# STM32Fx.net
KiCad netlist of a schematic drawn in Altium Designer
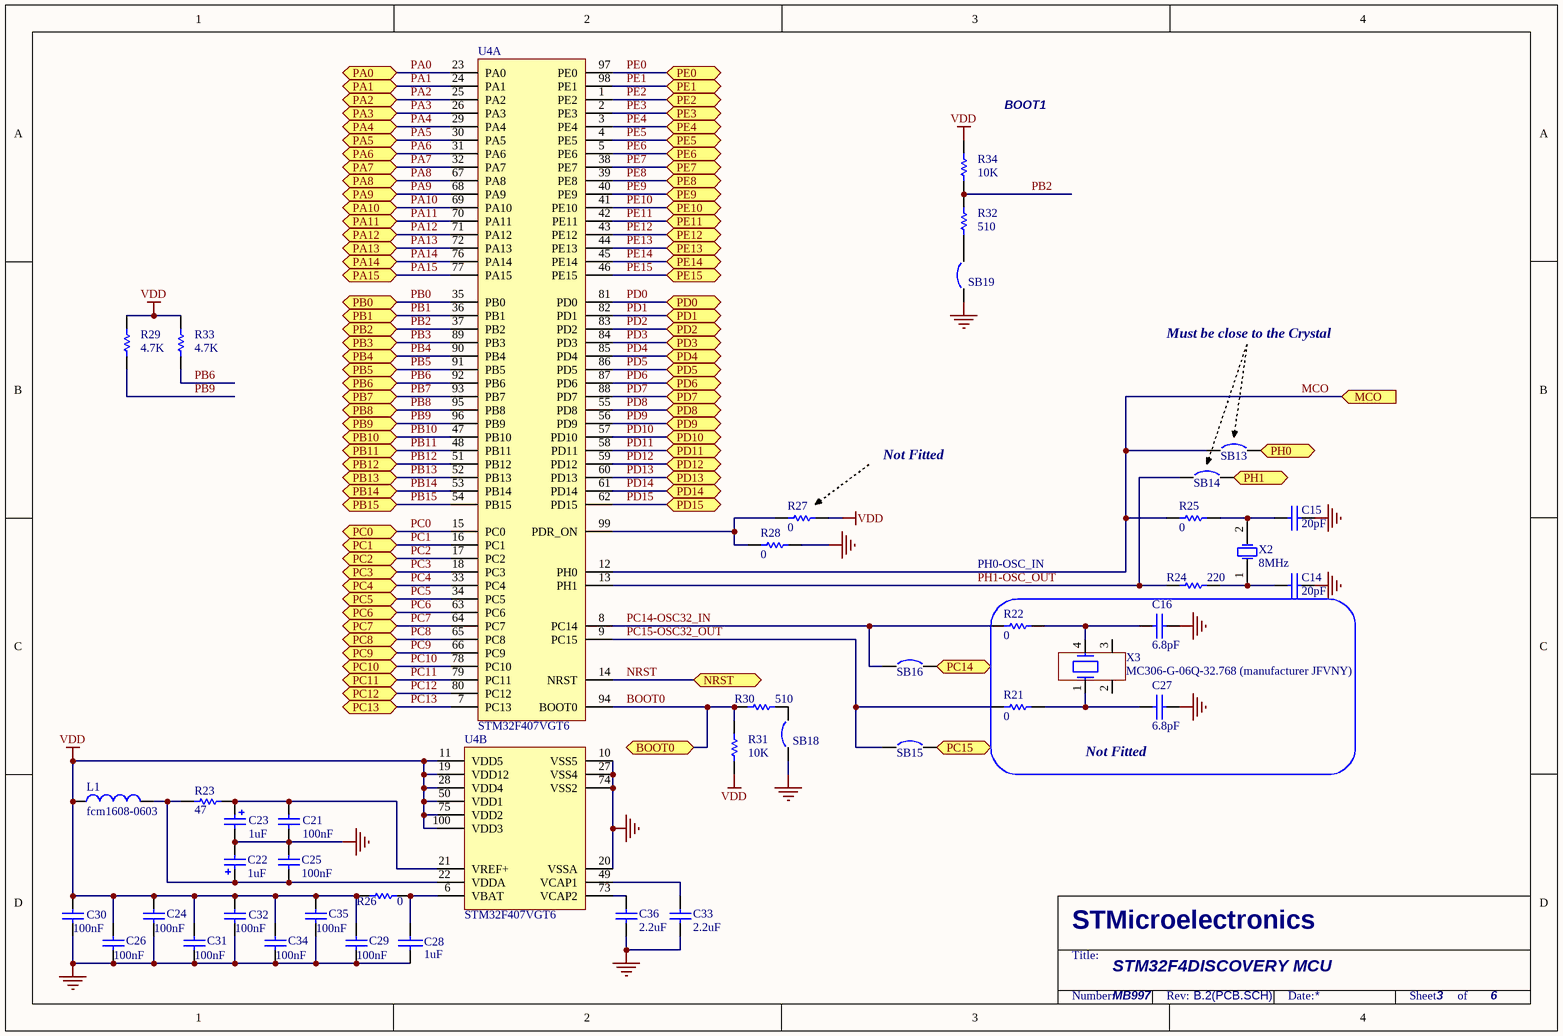
[diagram p0: STM32Fx.SchDoc]

(export (version "E")
  (design (tool "Eeschema 10.0.6"))
  (components
    (comp (ref "C14")
      (value "20pF")
      (footprint "0603C")
      (description "Capacitor")
      (libsource (lib "*") (part "CAP"))
    )
    (comp (ref "C15")
      (value "20pF")
      (footprint "0603C")
      (description "Capacitor")
      (libsource (lib "*") (part "CAP"))
    )
    (comp (ref "C16")
      (value "6.8pF")
      (footprint "0603C")
      (description "Capacitor")
      (libsource (lib "") (part "CAP_1"))
    )
    (comp (ref "C21")
      (value "100nF")
      (footprint "0603C")
      (description "Capacitor")
      (fields (field (name "PUBLISHER") "Altium Limited"))
      (libsource (lib "MB915_1") (part "Cap"))
    )
    (comp (ref "C22")
      (value "1uF")
      (footprint "CASE-AA")
      (description "Polarized Capacitor (Radial)")
      (fields (field (name "PUBLISHER") "Altium Limited"))
      (libsource (lib "Miscellaneous Devices") (part "Cap Pol1"))
    )
    (comp (ref "C23")
      (value "1uF")
      (footprint "CASE-AA")
      (description "Polarized Capacitor (Radial)")
      (fields (field (name "PUBLISHER") "Altium Limited"))
      (libsource (lib "Miscellaneous Devices") (part "Cap Pol1"))
    )
    (comp (ref "C24")
      (value "100nF")
      (footprint "0603C")
      (description "Capacitor")
      (fields (field (name "PUBLISHER") "Altium Limited"))
      (libsource (lib "MB915_1") (part "Cap"))
    )
    (comp (ref "C25")
      (value "100nF")
      (footprint "0603C")
      (description "Capacitor")
      (fields (field (name "PUBLISHER") "Altium Limited"))
      (libsource (lib "MB915_1") (part "Cap"))
    )
    (comp (ref "C26")
      (value "100nF")
      (footprint "0603C")
      (description "Capacitor")
      (fields (field (name "PUBLISHER") "Altium Limited"))
      (libsource (lib "MB915_1") (part "Cap"))
    )
    (comp (ref "C27")
      (value "6.8pF")
      (footprint "0603C")
      (description "Capacitor")
      (libsource (lib "") (part "CAP_1"))
    )
    (comp (ref "C28")
      (value "1uF")
      (footprint "0603C")
      (description "Capacitor")
      (libsource (lib "*") (part "CAP"))
    )
    (comp (ref "C29")
      (value "100nF")
      (footprint "0603C")
      (description "Capacitor")
      (fields (field (name "PUBLISHER") "Altium Limited"))
      (libsource (lib "MB915_1") (part "Cap"))
    )
    (comp (ref "C30")
      (value "100nF")
      (footprint "0603C")
      (description "Capacitor")
      (fields (field (name "PUBLISHER") "Altium Limited"))
      (libsource (lib "MB915_1") (part "Cap"))
    )
    (comp (ref "C31")
      (value "100nF")
      (footprint "0603C")
      (description "Capacitor")
      (fields (field (name "PUBLISHER") "Altium Limited"))
      (libsource (lib "MB915_1") (part "Cap"))
    )
    (comp (ref "C32")
      (value "100nF")
      (footprint "0603C")
      (description "Capacitor")
      (fields (field (name "PUBLISHER") "Altium Limited"))
      (libsource (lib "MB915_1") (part "Cap"))
    )
    (comp (ref "C33")
      (value "2.2uF")
      (footprint "CASE-A")
      (description "Low ESR Ceramic Capacitor (X7R)")
      (fields (field (name "PUBLISHER") "Altium Limited"))
      (libsource (lib "MB997") (part "Cap Low ESR"))
    )
    (comp (ref "C34")
      (value "100nF")
      (footprint "0603C")
      (description "Capacitor")
      (fields (field (name "PUBLISHER") "Altium Limited"))
      (libsource (lib "MB915_1") (part "Cap"))
    )
    (comp (ref "C35")
      (value "100nF")
      (footprint "0603C")
      (description "Capacitor")
      (fields (field (name "PUBLISHER") "Altium Limited"))
      (libsource (lib "MB915_1") (part "Cap"))
    )
    (comp (ref "C36")
      (value "2.2uF")
      (footprint "CASE-A")
      (description "Low ESR Ceramic Capacitor (X7R)")
      (fields (field (name "PUBLISHER") "Altium Limited"))
      (libsource (lib "MB997") (part "Cap Low ESR"))
    )
    (comp (ref "L1")
      (value "fcm1608-0603")
      (footprint "0603L")
      (description "Inductor")
      (fields (field (name "PUBLISHER") "Altium Limited"))
      (libsource (lib "Miscellaneous Devices") (part "Inductor"))
    )
    (comp (ref "R21")
      (value "0")
      (footprint "0603R")
      (description "Resistor")
      (fields (field (name "PUBLISHER") "Altium Limited"))
      (libsource (lib "Miscellaneous Devices") (part "Res1"))
    )
    (comp (ref "R22")
      (value "0")
      (footprint "0603R")
      (description "Resistor")
      (fields (field (name "PUBLISHER") "Altium Limited"))
      (libsource (lib "Miscellaneous Devices") (part "Res1"))
    )
    (comp (ref "R23")
      (value "47")
      (footprint "0603R")
      (description "Resistor")
      (fields (field (name "PUBLISHER") "Altium Limited"))
      (libsource (lib "Miscellaneous Devices") (part "Res1"))
    )
    (comp (ref "R24")
      (value "220")
      (footprint "0603R")
      (description "Resistor")
      (fields (field (name "PUBLISHER") "Altium Limited"))
      (libsource (lib "Miscellaneous Devices") (part "Res1"))
    )
    (comp (ref "R25")
      (value "0")
      (footprint "0603R")
      (description "Resistor")
      (fields (field (name "PUBLISHER") "Altium Limited"))
      (libsource (lib "Miscellaneous Devices") (part "Res1"))
    )
    (comp (ref "R26")
      (value "0")
      (footprint "0603R")
      (description "Resistor")
      (fields (field (name "PUBLISHER") "Altium Limited"))
      (libsource (lib "Miscellaneous Devices") (part "res1"))
    )
    (comp (ref "R27")
      (value "0")
      (footprint "0603R")
      (description "Resistor")
      (fields (field (name "PUBLISHER") "Altium Limited"))
      (libsource (lib "Miscellaneous Devices") (part "Res1"))
    )
    (comp (ref "R28")
      (value "0")
      (footprint "0603R")
      (description "Resistor")
      (fields (field (name "PUBLISHER") "Altium Limited"))
      (libsource (lib "Miscellaneous Devices") (part "Res1"))
    )
    (comp (ref "R29")
      (value "4.7K")
      (footprint "0402R")
      (description "Resistor")
      (fields (field (name "PUBLISHER") "Altium Limited"))
      (libsource (lib "Miscellaneous Devices") (part "res1"))
    )
    (comp (ref "R30")
      (value "510")
      (footprint "0603R")
      (description "Resistor")
      (fields (field (name "PUBLISHER") "Altium Limited"))
      (libsource (lib "Miscellaneous Devices") (part "Res1"))
    )
    (comp (ref "R31")
      (value "10K")
      (footprint "0402R")
      (description "Resistor")
      (fields (field (name "PUBLISHER") "Altium Limited"))
      (libsource (lib "Miscellaneous Devices") (part "res1"))
    )
    (comp (ref "R32")
      (value "510")
      (footprint "0603R")
      (description "Resistor")
      (fields (field (name "PUBLISHER") "Altium Limited"))
      (libsource (lib "Miscellaneous Devices") (part "res1"))
    )
    (comp (ref "R33")
      (value "4.7K")
      (footprint "0402R")
      (description "Resistor")
      (fields (field (name "PUBLISHER") "Altium Limited"))
      (libsource (lib "Miscellaneous Devices") (part "res1"))
    )
    (comp (ref "R34")
      (value "10K")
      (footprint "0402R")
      (description "Resistor")
      (fields (field (name "PUBLISHER") "Altium Limited"))
      (libsource (lib "Miscellaneous Devices") (part "res1"))
    )
    (comp (ref "SB13")
      (value "Circuit Breaker")
      (footprint "JP2_SMD")
      (fields (field (name "PUBLISHER") "Altium Limited"))
      (libsource (lib "MB915") (part "Circuit Breaker"))
    )
    (comp (ref "SB14")
      (value "Circuit Breaker")
      (footprint "JP2_SMD")
      (fields (field (name "PUBLISHER") "Altium Limited"))
      (libsource (lib "MB915") (part "Circuit Breaker"))
    )
    (comp (ref "SB15")
      (value "Circuit Breaker")
      (footprint "JP2_SMD")
      (fields (field (name "PUBLISHER") "Altium Limited"))
      (libsource (lib "MB915") (part "Circuit Breaker"))
    )
    (comp (ref "SB16")
      (value "Circuit Breaker")
      (footprint "JP2_SMD")
      (fields (field (name "PUBLISHER") "Altium Limited"))
      (libsource (lib "MB915") (part "Circuit Breaker"))
    )
    (comp (ref "SB18")
      (value "Circuit Breaker")
      (footprint "JP2_SMD")
      (fields (field (name "PUBLISHER") "Altium Limited"))
      (libsource (lib "MB915") (part "Circuit Breaker"))
    )
    (comp (ref "SB19")
      (value "Circuit Breaker")
      (footprint "JP2_SMD")
      (fields (field (name "PUBLISHER") "Altium Limited"))
      (libsource (lib "MB915") (part "Circuit Breaker"))
    )
    (comp (ref "U4")
      (value "STM32F407VGT6")
      (footprint "TQFP100")
      (description "STM32 Manta (STM32F407VGT6)")
      (libsource (lib "MB997") (part "STM32F407VGT6"))
    )
    (comp (ref "X2")
      (value "8MHz")
      (footprint "XTAL1")
      (description "Crystal Oscillator")
      (fields (field (name "PUBLISHER") "Altium Limited"))
      (libsource (lib "MB963_1") (part "XTAL"))
    )
    (comp (ref "X3")
      (value "MC306-G-06Q-32.768 (manufacturer JFVNY)")
      (footprint "MC306-CRYSTAL")
      (libsource (lib "*") (part "MC306"))
    )
  )
  (nets
    (net (code "1") (name "/BOOT0") (class "Default")
      (node (ref "R30") (pin "2") (pinfunction "2_2") (pintype "passive"))
      (node (ref "R31") (pin "1") (pinfunction "1_1") (pintype "passive"))
      (node (ref "U4") (pin "94") (pinfunction "BOOT0_94") (pintype "passive"))
    )
    (net (code "2") (name "/MCO") (class "Default")
      (node (ref "R25") (pin "1") (pinfunction "1_1") (pintype "passive"))
      (node (ref "SB13") (pin "1") (pinfunction "1_1") (pintype "passive"))
      (node (ref "U4") (pin "12") (pinfunction "PH0_12") (pintype "passive"))
    )
    (net (code "3") (name "/NRST") (class "Default")
      (node (ref "U4") (pin "14") (pinfunction "NRST_14") (pintype "passive"))
    )
    (net (code "4") (name "/PA0") (class "Default")
      (node (ref "U4") (pin "23") (pinfunction "PA0_23") (pintype "passive"))
    )
    (net (code "5") (name "/PA1") (class "Default")
      (node (ref "U4") (pin "24") (pinfunction "PA1_24") (pintype "passive"))
    )
    (net (code "6") (name "/PA2") (class "Default")
      (node (ref "U4") (pin "25") (pinfunction "PA2_25") (pintype "passive"))
    )
    (net (code "7") (name "/PA3") (class "Default")
      (node (ref "U4") (pin "26") (pinfunction "PA3_26") (pintype "passive"))
    )
    (net (code "8") (name "/PA4") (class "Default")
      (node (ref "U4") (pin "29") (pinfunction "PA4_29") (pintype "passive"))
    )
    (net (code "9") (name "/PA5") (class "Default")
      (node (ref "U4") (pin "30") (pinfunction "PA5_30") (pintype "passive"))
    )
    (net (code "10") (name "/PA6") (class "Default")
      (node (ref "U4") (pin "31") (pinfunction "PA6_31") (pintype "passive"))
    )
    (net (code "11") (name "/PA7") (class "Default")
      (node (ref "U4") (pin "32") (pinfunction "PA7_32") (pintype "passive"))
    )
    (net (code "12") (name "/PA8") (class "Default")
      (node (ref "U4") (pin "67") (pinfunction "PA8_67") (pintype "passive"))
    )
    (net (code "13") (name "/PA9") (class "Default")
      (node (ref "U4") (pin "68") (pinfunction "PA9_68") (pintype "passive"))
    )
    (net (code "14") (name "/PA10") (class "Default")
      (node (ref "U4") (pin "69") (pinfunction "PA10_69") (pintype "passive"))
    )
    (net (code "15") (name "/PA11") (class "Default")
      (node (ref "U4") (pin "70") (pinfunction "PA11_70") (pintype "passive"))
    )
    (net (code "16") (name "/PA12") (class "Default")
      (node (ref "U4") (pin "71") (pinfunction "PA12_71") (pintype "passive"))
    )
    (net (code "17") (name "/PA13") (class "Default")
      (node (ref "U4") (pin "72") (pinfunction "PA13_72") (pintype "passive"))
    )
    (net (code "18") (name "/PA14") (class "Default")
      (node (ref "U4") (pin "76") (pinfunction "PA14_76") (pintype "passive"))
    )
    (net (code "19") (name "/PA15") (class "Default")
      (node (ref "U4") (pin "77") (pinfunction "PA15_77") (pintype "passive"))
    )
    (net (code "20") (name "/PB0") (class "Default")
      (node (ref "U4") (pin "35") (pinfunction "PB0_35") (pintype "passive"))
    )
    (net (code "21") (name "/PB1") (class "Default")
      (node (ref "U4") (pin "36") (pinfunction "PB1_36") (pintype "passive"))
    )
    (net (code "22") (name "/PB2") (class "Default")
      (node (ref "R32") (pin "1") (pinfunction "1_1") (pintype "passive"))
      (node (ref "R34") (pin "2") (pinfunction "2_2") (pintype "passive"))
      (node (ref "U4") (pin "37") (pinfunction "PB2_37") (pintype "passive"))
    )
    (net (code "23") (name "/PB3") (class "Default")
      (node (ref "U4") (pin "89") (pinfunction "PB3_89") (pintype "passive"))
    )
    (net (code "24") (name "/PB4") (class "Default")
      (node (ref "U4") (pin "90") (pinfunction "PB4_90") (pintype "passive"))
    )
    (net (code "25") (name "/PB5") (class "Default")
      (node (ref "U4") (pin "91") (pinfunction "PB5_91") (pintype "passive"))
    )
    (net (code "26") (name "/PB6") (class "Default")
      (node (ref "R33") (pin "2") (pinfunction "2_2") (pintype "passive"))
      (node (ref "U4") (pin "92") (pinfunction "PB6_92") (pintype "passive"))
    )
    (net (code "27") (name "/PB7") (class "Default")
      (node (ref "U4") (pin "93") (pinfunction "PB7_93") (pintype "passive"))
    )
    (net (code "28") (name "/PB8") (class "Default")
      (node (ref "U4") (pin "95") (pinfunction "PB8_95") (pintype "passive"))
    )
    (net (code "29") (name "/PB9") (class "Default")
      (node (ref "R29") (pin "2") (pinfunction "2_2") (pintype "passive"))
      (node (ref "U4") (pin "96") (pinfunction "PB9_96") (pintype "passive"))
    )
    (net (code "30") (name "/PB10") (class "Default")
      (node (ref "U4") (pin "47") (pinfunction "PB10_47") (pintype "passive"))
    )
    (net (code "31") (name "/PB11") (class "Default")
      (node (ref "U4") (pin "48") (pinfunction "PB11_48") (pintype "passive"))
    )
    (net (code "32") (name "/PB12") (class "Default")
      (node (ref "U4") (pin "51") (pinfunction "PB12_51") (pintype "passive"))
    )
    (net (code "33") (name "/PB13") (class "Default")
      (node (ref "U4") (pin "52") (pinfunction "PB13_52") (pintype "passive"))
    )
    (net (code "34") (name "/PB14") (class "Default")
      (node (ref "U4") (pin "53") (pinfunction "PB14_53") (pintype "passive"))
    )
    (net (code "35") (name "/PB15") (class "Default")
      (node (ref "U4") (pin "54") (pinfunction "PB15_54") (pintype "passive"))
    )
    (net (code "36") (name "/PC0") (class "Default")
      (node (ref "U4") (pin "15") (pinfunction "PC0_15") (pintype "passive"))
    )
    (net (code "37") (name "/PC1") (class "Default")
      (node (ref "U4") (pin "16") (pinfunction "PC1_16") (pintype "passive"))
    )
    (net (code "38") (name "/PC2") (class "Default")
      (node (ref "U4") (pin "17") (pinfunction "PC2_17") (pintype "passive"))
    )
    (net (code "39") (name "/PC3") (class "Default")
      (node (ref "U4") (pin "18") (pinfunction "PC3_18") (pintype "passive"))
    )
    (net (code "40") (name "/PC4") (class "Default")
      (node (ref "U4") (pin "33") (pinfunction "PC4_33") (pintype "passive"))
    )
    (net (code "41") (name "/PC5") (class "Default")
      (node (ref "U4") (pin "34") (pinfunction "PC5_34") (pintype "passive"))
    )
    (net (code "42") (name "/PC6") (class "Default")
      (node (ref "U4") (pin "63") (pinfunction "PC6_63") (pintype "passive"))
    )
    (net (code "43") (name "/PC7") (class "Default")
      (node (ref "U4") (pin "64") (pinfunction "PC7_64") (pintype "passive"))
    )
    (net (code "44") (name "/PC8") (class "Default")
      (node (ref "U4") (pin "65") (pinfunction "PC8_65") (pintype "passive"))
    )
    (net (code "45") (name "/PC9") (class "Default")
      (node (ref "U4") (pin "66") (pinfunction "PC9_66") (pintype "passive"))
    )
    (net (code "46") (name "/PC10") (class "Default")
      (node (ref "U4") (pin "78") (pinfunction "PC10_78") (pintype "passive"))
    )
    (net (code "47") (name "/PC11") (class "Default")
      (node (ref "U4") (pin "79") (pinfunction "PC11_79") (pintype "passive"))
    )
    (net (code "48") (name "/PC12") (class "Default")
      (node (ref "U4") (pin "80") (pinfunction "PC12_80") (pintype "passive"))
    )
    (net (code "49") (name "/PC13") (class "Default")
      (node (ref "U4") (pin "7") (pinfunction "PC13_7") (pintype "passive"))
    )
    (net (code "50") (name "/PC14") (class "Default")
      (node (ref "SB16") (pin "2") (pinfunction "2_2") (pintype "passive"))
    )
    (net (code "51") (name "/PC14-OSC32_IN") (class "Default")
      (node (ref "R22") (pin "1") (pinfunction "1_1") (pintype "passive"))
      (node (ref "SB16") (pin "1") (pinfunction "1_1") (pintype "passive"))
      (node (ref "U4") (pin "8") (pinfunction "PC14_8") (pintype "passive"))
    )
    (net (code "52") (name "/PC15") (class "Default")
      (node (ref "SB15") (pin "2") (pinfunction "2_2") (pintype "passive"))
    )
    (net (code "53") (name "/PC15-OSC32_OUT") (class "Default")
      (node (ref "R21") (pin "1") (pinfunction "1_1") (pintype "passive"))
      (node (ref "SB15") (pin "1") (pinfunction "1_1") (pintype "passive"))
      (node (ref "U4") (pin "9") (pinfunction "PC15_9") (pintype "passive"))
    )
    (net (code "54") (name "/PD0") (class "Default")
      (node (ref "U4") (pin "81") (pinfunction "PD0_81") (pintype "passive"))
    )
    (net (code "55") (name "/PD1") (class "Default")
      (node (ref "U4") (pin "82") (pinfunction "PD1_82") (pintype "passive"))
    )
    (net (code "56") (name "/PD2") (class "Default")
      (node (ref "U4") (pin "83") (pinfunction "PD2_83") (pintype "passive"))
    )
    (net (code "57") (name "/PD3") (class "Default")
      (node (ref "U4") (pin "84") (pinfunction "PD3_84") (pintype "passive"))
    )
    (net (code "58") (name "/PD4") (class "Default")
      (node (ref "U4") (pin "85") (pinfunction "PD4_85") (pintype "passive"))
    )
    (net (code "59") (name "/PD5") (class "Default")
      (node (ref "U4") (pin "86") (pinfunction "PD5_86") (pintype "passive"))
    )
    (net (code "60") (name "/PD6") (class "Default")
      (node (ref "U4") (pin "87") (pinfunction "PD6_87") (pintype "passive"))
    )
    (net (code "61") (name "/PD7") (class "Default")
      (node (ref "U4") (pin "88") (pinfunction "PD7_88") (pintype "passive"))
    )
    (net (code "62") (name "/PD8") (class "Default")
      (node (ref "U4") (pin "55") (pinfunction "PD8_55") (pintype "passive"))
    )
    (net (code "63") (name "/PD9") (class "Default")
      (node (ref "U4") (pin "56") (pinfunction "PD9_56") (pintype "passive"))
    )
    (net (code "64") (name "/PD10") (class "Default")
      (node (ref "U4") (pin "57") (pinfunction "PD10_57") (pintype "passive"))
    )
    (net (code "65") (name "/PD11") (class "Default")
      (node (ref "U4") (pin "58") (pinfunction "PD11_58") (pintype "passive"))
    )
    (net (code "66") (name "/PD12") (class "Default")
      (node (ref "U4") (pin "59") (pinfunction "PD12_59") (pintype "passive"))
    )
    (net (code "67") (name "/PD13") (class "Default")
      (node (ref "U4") (pin "60") (pinfunction "PD13_60") (pintype "passive"))
    )
    (net (code "68") (name "/PD14") (class "Default")
      (node (ref "U4") (pin "61") (pinfunction "PD14_61") (pintype "passive"))
    )
    (net (code "69") (name "/PD15") (class "Default")
      (node (ref "U4") (pin "62") (pinfunction "PD15_62") (pintype "passive"))
    )
    (net (code "70") (name "/PE0") (class "Default")
      (node (ref "U4") (pin "97") (pinfunction "PE0_97") (pintype "passive"))
    )
    (net (code "71") (name "/PE1") (class "Default")
      (node (ref "U4") (pin "98") (pinfunction "PE1_98") (pintype "passive"))
    )
    (net (code "72") (name "/PE2") (class "Default")
      (node (ref "U4") (pin "1") (pinfunction "PE2_1") (pintype "passive"))
    )
    (net (code "73") (name "/PE3") (class "Default")
      (node (ref "U4") (pin "2") (pinfunction "PE3_2") (pintype "passive"))
    )
    (net (code "74") (name "/PE4") (class "Default")
      (node (ref "U4") (pin "3") (pinfunction "PE4_3") (pintype "passive"))
    )
    (net (code "75") (name "/PE5") (class "Default")
      (node (ref "U4") (pin "4") (pinfunction "PE5_4") (pintype "passive"))
    )
    (net (code "76") (name "/PE6") (class "Default")
      (node (ref "U4") (pin "5") (pinfunction "PE6_5") (pintype "passive"))
    )
    (net (code "77") (name "/PE7") (class "Default")
      (node (ref "U4") (pin "38") (pinfunction "PE7_38") (pintype "passive"))
    )
    (net (code "78") (name "/PE8") (class "Default")
      (node (ref "U4") (pin "39") (pinfunction "PE8_39") (pintype "passive"))
    )
    (net (code "79") (name "/PE9") (class "Default")
      (node (ref "U4") (pin "40") (pinfunction "PE9_40") (pintype "passive"))
    )
    (net (code "80") (name "/PE10") (class "Default")
      (node (ref "U4") (pin "41") (pinfunction "PE10_41") (pintype "passive"))
    )
    (net (code "81") (name "/PE11") (class "Default")
      (node (ref "U4") (pin "42") (pinfunction "PE11_42") (pintype "passive"))
    )
    (net (code "82") (name "/PE12") (class "Default")
      (node (ref "U4") (pin "43") (pinfunction "PE12_43") (pintype "passive"))
    )
    (net (code "83") (name "/PE13") (class "Default")
      (node (ref "U4") (pin "44") (pinfunction "PE13_44") (pintype "passive"))
    )
    (net (code "84") (name "/PE14") (class "Default")
      (node (ref "U4") (pin "45") (pinfunction "PE14_45") (pintype "passive"))
    )
    (net (code "85") (name "/PE15") (class "Default")
      (node (ref "U4") (pin "46") (pinfunction "PE15_46") (pintype "passive"))
    )
    (net (code "86") (name "/PH0") (class "Default")
      (node (ref "SB13") (pin "2") (pinfunction "2_2") (pintype "passive"))
    )
    (net (code "87") (name "/PH1") (class "Default")
      (node (ref "SB14") (pin "2") (pinfunction "2_2") (pintype "passive"))
    )
    (net (code "88") (name "/PH1-OSC_OUT") (class "Default")
      (node (ref "R24") (pin "2") (pinfunction "2_2") (pintype "passive"))
      (node (ref "SB14") (pin "1") (pinfunction "1_1") (pintype "passive"))
      (node (ref "U4") (pin "13") (pinfunction "PH1_13") (pintype "passive"))
    )
    (net (code "89") (name "GND") (class "Default")
      (node (ref "C14") (pin "1") (pinfunction "1_1") (pintype "passive"))
      (node (ref "C15") (pin "1") (pinfunction "1_1") (pintype "passive"))
      (node (ref "C16") (pin "2") (pinfunction "2_2") (pintype "passive"))
      (node (ref "C21") (pin "1") (pinfunction "1_1") (pintype "passive"))
      (node (ref "C22") (pin "2") (pinfunction "2_2") (pintype "passive"))
      (node (ref "C23") (pin "2") (pinfunction "2_2") (pintype "passive"))
      (node (ref "C24") (pin "2") (pinfunction "2_2") (pintype "passive"))
      (node (ref "C25") (pin "1") (pinfunction "1_1") (pintype "passive"))
      (node (ref "C26") (pin "1") (pinfunction "1_1") (pintype "passive"))
      (node (ref "C27") (pin "2") (pinfunction "2_2") (pintype "passive"))
      (node (ref "C28") (pin "2") (pinfunction "2_2") (pintype "passive"))
      (node (ref "C29") (pin "1") (pinfunction "1_1") (pintype "passive"))
      (node (ref "C30") (pin "1") (pinfunction "1_1") (pintype "passive"))
      (node (ref "C31") (pin "1") (pinfunction "1_1") (pintype "passive"))
      (node (ref "C32") (pin "1") (pinfunction "1_1") (pintype "passive"))
      (node (ref "C33") (pin "2") (pinfunction "2_2") (pintype "passive"))
      (node (ref "C34") (pin "1") (pinfunction "1_1") (pintype "passive"))
      (node (ref "C35") (pin "2") (pinfunction "2_2") (pintype "passive"))
      (node (ref "C36") (pin "2") (pinfunction "2_2") (pintype "passive"))
      (node (ref "R28") (pin "2") (pinfunction "2_2") (pintype "passive"))
      (node (ref "SB18") (pin "1") (pinfunction "1_1") (pintype "passive"))
      (node (ref "SB19") (pin "1") (pinfunction "1_1") (pintype "passive"))
      (node (ref "U4") (pin "10") (pinfunction "VSS5_10") (pintype "passive"))
      (node (ref "U4") (pin "20") (pinfunction "VSSA_20") (pintype "passive"))
      (node (ref "U4") (pin "27") (pinfunction "VSS4_27") (pintype "passive"))
      (node (ref "U4") (pin "74") (pinfunction "VSS2_74") (pintype "passive"))
    )
    (net (code "90") (name "Net-(C16-Pad1)") (class "Default")
      (node (ref "C16") (pin "1") (pinfunction "1_1") (pintype "passive"))
      (node (ref "R22") (pin "2") (pinfunction "2_2") (pintype "passive"))
      (node (ref "X3") (pin "4") (pinfunction "4_4") (pintype "passive"))
    )
    (net (code "91") (name "Net-(C27-Pad1)") (class "Default")
      (node (ref "C27") (pin "1") (pinfunction "1_1") (pintype "passive"))
      (node (ref "R21") (pin "2") (pinfunction "2_2") (pintype "passive"))
      (node (ref "X3") (pin "1") (pinfunction "1_1") (pintype "passive"))
    )
    (net (code "92") (name "Net-(R30-Pad1)") (class "Default")
      (node (ref "R30") (pin "1") (pinfunction "1_1") (pintype "passive"))
      (node (ref "SB18") (pin "2") (pinfunction "2_2") (pintype "passive"))
    )
    (net (code "93") (name "Net-(R32-Pad2)") (class "Default")
      (node (ref "R32") (pin "2") (pinfunction "2_2") (pintype "passive"))
      (node (ref "SB19") (pin "2") (pinfunction "2_2") (pintype "passive"))
    )
    (net (code "94") (name "Net-(U4A-PDR_ON)") (class "Default")
      (node (ref "R27") (pin "1") (pinfunction "1_1") (pintype "passive"))
      (node (ref "R28") (pin "1") (pinfunction "1_1") (pintype "passive"))
      (node (ref "U4") (pin "99") (pinfunction "PDR_ON_99") (pintype "passive"))
    )
    (net (code "95") (name "Net-(U4B-VBAT)") (class "Default")
      (node (ref "C28") (pin "1") (pinfunction "1_1") (pintype "passive"))
      (node (ref "R26") (pin "2") (pinfunction "2_2") (pintype "passive"))
      (node (ref "U4") (pin "6") (pinfunction "VBAT_6") (pintype "passive"))
    )
    (net (code "96") (name "Net-(U4B-VCAP1)") (class "Default")
      (node (ref "C33") (pin "1") (pinfunction "1_1") (pintype "passive"))
      (node (ref "U4") (pin "49") (pinfunction "VCAP1_49") (pintype "passive"))
    )
    (net (code "97") (name "Net-(U4B-VCAP2)") (class "Default")
      (node (ref "C36") (pin "1") (pinfunction "1_1") (pintype "passive"))
      (node (ref "U4") (pin "73") (pinfunction "VCAP2_73") (pintype "passive"))
    )
    (net (code "98") (name "Net-(U4B-VDDA)") (class "Default")
      (node (ref "C22") (pin "1") (pinfunction "1_1") (pintype "passive"))
      (node (ref "C25") (pin "2") (pinfunction "2_2") (pintype "passive"))
      (node (ref "L1") (pin "2") (pinfunction "2_2") (pintype "passive"))
      (node (ref "R23") (pin "2") (pinfunction "2_2") (pintype "passive"))
      (node (ref "U4") (pin "22") (pinfunction "VDDA_22") (pintype "passive"))
    )
    (net (code "99") (name "Net-(U4B-VREF+)") (class "Default")
      (node (ref "C21") (pin "2") (pinfunction "2_2") (pintype "passive"))
      (node (ref "C23") (pin "1") (pinfunction "1_1") (pintype "passive"))
      (node (ref "R23") (pin "1") (pinfunction "1_1") (pintype "passive"))
      (node (ref "U4") (pin "21") (pinfunction "VREF+_21") (pintype "passive"))
    )
    (net (code "100") (name "Net-(X2-OSC1)") (class "Default")
      (node (ref "C14") (pin "2") (pinfunction "2_2") (pintype "passive"))
      (node (ref "R24") (pin "1") (pinfunction "1_1") (pintype "passive"))
      (node (ref "X2") (pin "1") (pinfunction "OSC1_1") (pintype "passive"))
    )
    (net (code "101") (name "Net-(X2-OSC2)") (class "Default")
      (node (ref "C15") (pin "2") (pinfunction "2_2") (pintype "passive"))
      (node (ref "R25") (pin "2") (pinfunction "2_2") (pintype "passive"))
      (node (ref "X2") (pin "2") (pinfunction "OSC2_2") (pintype "passive"))
    )
    (net (code "102") (name "VDD") (class "Default")
      (node (ref "C24") (pin "1") (pinfunction "1_1") (pintype "passive"))
      (node (ref "C26") (pin "2") (pinfunction "2_2") (pintype "passive"))
      (node (ref "C29") (pin "2") (pinfunction "2_2") (pintype "passive"))
      (node (ref "C30") (pin "2") (pinfunction "2_2") (pintype "passive"))
      (node (ref "C31") (pin "2") (pinfunction "2_2") (pintype "passive"))
      (node (ref "C32") (pin "2") (pinfunction "2_2") (pintype "passive"))
      (node (ref "C34") (pin "2") (pinfunction "2_2") (pintype "passive"))
      (node (ref "C35") (pin "1") (pinfunction "1_1") (pintype "passive"))
      (node (ref "L1") (pin "1") (pinfunction "1_1") (pintype "passive"))
      (node (ref "R26") (pin "1") (pinfunction "1_1") (pintype "passive"))
      (node (ref "R27") (pin "2") (pinfunction "2_2") (pintype "passive"))
      (node (ref "R29") (pin "1") (pinfunction "1_1") (pintype "passive"))
      (node (ref "R31") (pin "2") (pinfunction "2_2") (pintype "passive"))
      (node (ref "R33") (pin "1") (pinfunction "1_1") (pintype "passive"))
      (node (ref "R34") (pin "1") (pinfunction "1_1") (pintype "passive"))
      (node (ref "U4") (pin "100") (pinfunction "VDD3_100") (pintype "passive"))
      (node (ref "U4") (pin "11") (pinfunction "VDD5_11") (pintype "passive"))
      (node (ref "U4") (pin "19") (pinfunction "VDD12_19") (pintype "passive"))
      (node (ref "U4") (pin "28") (pinfunction "VDD4_28") (pintype "passive"))
      (node (ref "U4") (pin "50") (pinfunction "VDD1_50") (pintype "passive"))
      (node (ref "U4") (pin "75") (pinfunction "VDD2_75") (pintype "passive"))
    )
    (net (code "103") (name "unconnected-(X3-Pad2)") (class "Default")
      (node (ref "X3") (pin "2") (pinfunction "2_2") (pintype "passive"))
    )
    (net (code "104") (name "unconnected-(X3-Pad3)") (class "Default")
      (node (ref "X3") (pin "3") (pinfunction "3_3") (pintype "passive"))
    )
  )
)
